# SNES_PicoCIC_v1_0.net
KiCad netlist of a schematic drawn in Altium Designer
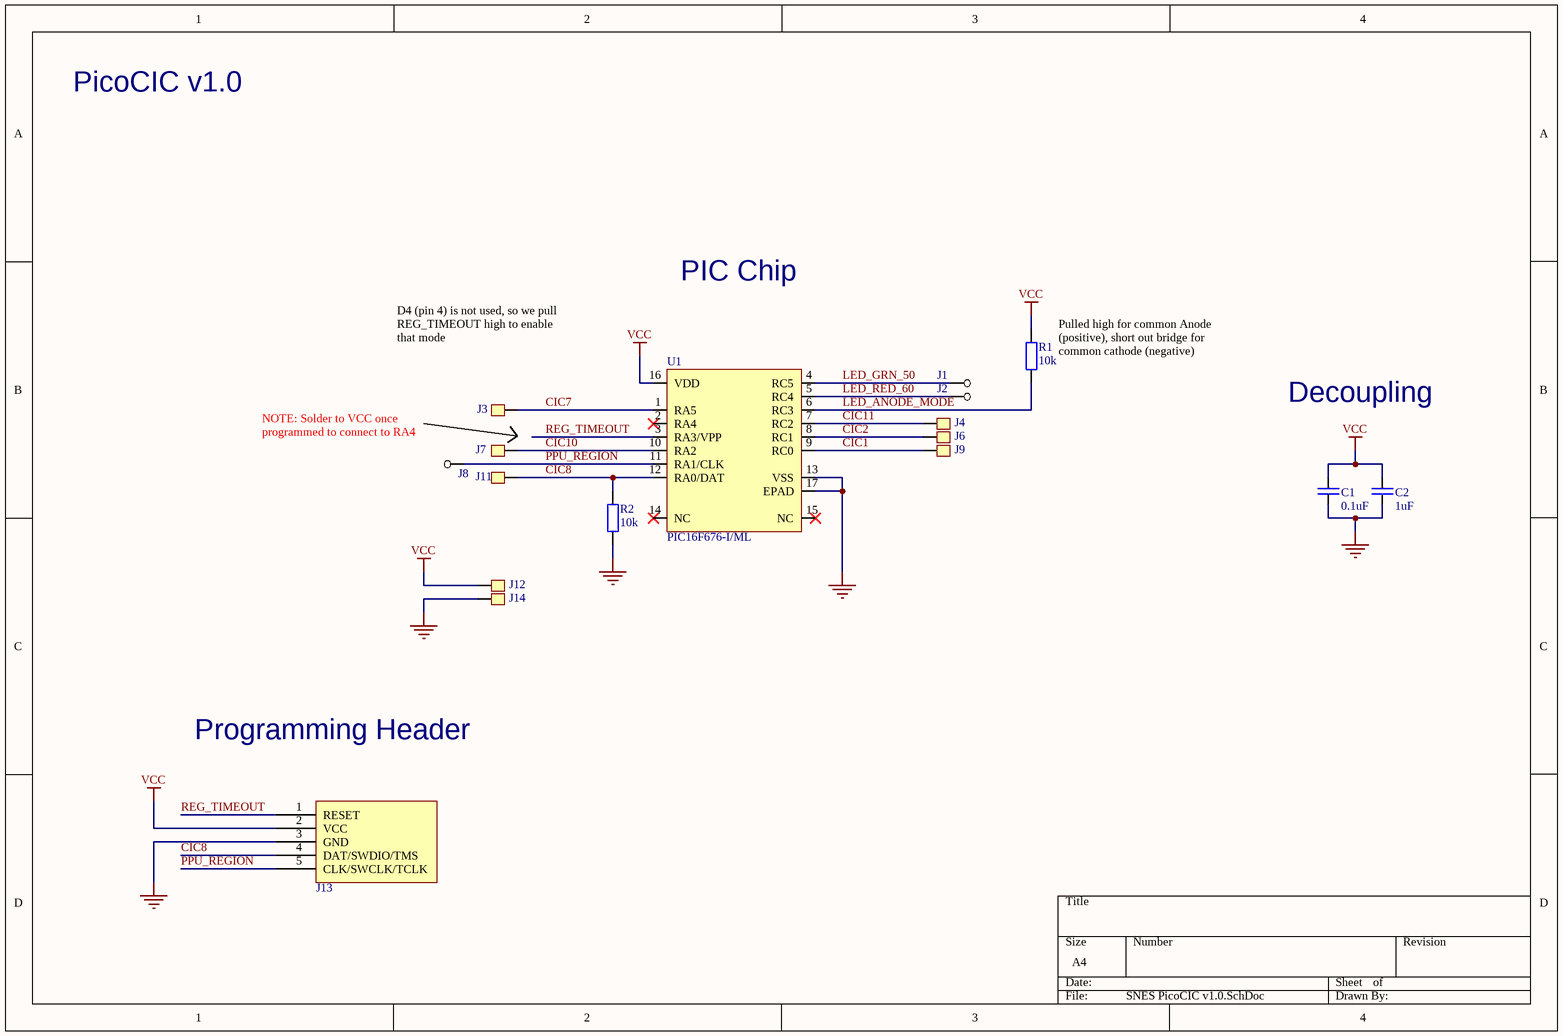
[diagram p0: SNES PicoCIC v1.0.SchDoc]

(export (version "E")
  (design (tool "Eeschema 10.0.6"))
  (components
    (comp (ref "C1")
      (value "0.1uF")
      (footprint "C0402")
      (description "Capacitor Ceramic 0.1uF 16V X5R 0402")
      (fields
        (field (name "MANUFACTURER") "Yageo")
        (field (name "MANUFACTURER PART NUMBER") "CC0402KRX7R7BB104")
      )
      (libsource (lib "Integrated_Library") (part "CAP_0UF1_0402"))
    )
    (comp (ref "C2")
      (value "1uF")
      (footprint "C0402")
      (description "Capacitor Ceramic 1uF 10V X5R 0402")
      (fields
        (field (name "MANUFACTURER") "Murata Electronics North America")
        (field (name "MANUFACTURER PART NUMBER") "GRM155R61A105KE15D")
      )
      (libsource (lib "Integrated_Library") (part "CAP_1UF_0402"))
    )
    (comp (ref "J1")
      (value "SP")
      (footprint "SP1.5")
      (description "Solder pad")
      (libsource (lib "Integrated_Library") (part "SP"))
    )
    (comp (ref "J2")
      (value "SP")
      (footprint "SP1.5")
      (description "Solder pad")
      (libsource (lib "Integrated_Library") (part "SP"))
    )
    (comp (ref "J3")
      (value "0.8MM Castellated Pad")
      (footprint "0.8MM CASTELLATED PAD")
      (description "Castellated pad for 0.8mm pitch")
      (libsource (lib "") (part "0.8MM Castellated Pad_1"))
    )
    (comp (ref "J4")
      (value "0.8MM Castellated Pad")
      (footprint "0.8MM CASTELLATED PAD")
      (description "Castellated pad for 0.8mm pitch")
      (libsource (lib "Integrated_Library") (part "0.8MM Castellated Pad"))
    )
    (comp (ref "J6")
      (value "0.8MM Castellated Pad")
      (footprint "0.8MM CASTELLATED PAD")
      (description "Castellated pad for 0.8mm pitch")
      (libsource (lib "Integrated_Library") (part "0.8MM Castellated Pad"))
    )
    (comp (ref "J7")
      (value "0.8MM Castellated Pad")
      (footprint "0.8MM CASTELLATED PAD")
      (description "Castellated pad for 0.8mm pitch")
      (libsource (lib "") (part "0.8MM Castellated Pad_1"))
    )
    (comp (ref "J8")
      (value "SP")
      (footprint "SP1.5")
      (description "Solder pad")
      (libsource (lib "Integrated_Library") (part "SP"))
    )
    (comp (ref "J9")
      (value "0.8MM Castellated Pad")
      (footprint "0.8MM CASTELLATED PAD")
      (description "Castellated pad for 0.8mm pitch")
      (libsource (lib "Integrated_Library") (part "0.8MM Castellated Pad"))
    )
    (comp (ref "J11")
      (value "0.8MM Castellated Pad")
      (footprint "0.8MM CASTELLATED PAD")
      (description "Castellated pad for 0.8mm pitch")
      (libsource (lib "") (part "0.8MM Castellated Pad_1"))
    )
    (comp (ref "J12")
      (value "0.8MM Castellated Pad")
      (footprint "0.8MM CASTELLATED PAD")
      (description "Castellated pad for 0.8mm pitch")
      (libsource (lib "Integrated_Library") (part "0.8MM Castellated Pad"))
    )
    (comp (ref "J13")
      (value "JTAG-SWD2")
      (footprint "JTAG-SWD 1.28mm")
      (description "JTAG-SWD Connector")
      (libsource (lib "Integrated_Library") (part "JTAG-SWD2"))
    )
    (comp (ref "J14")
      (value "0.8MM Castellated Pad")
      (footprint "0.8MM CASTELLATED PAD")
      (description "Castellated pad for 0.8mm pitch")
      (libsource (lib "Integrated_Library") (part "0.8MM Castellated Pad"))
    )
    (comp (ref "R1")
      (value "10k")
      (footprint "R0201")
      (description "Resistor 10k 0.05W 0201")
      (fields
        (field (name "MANUFACTURER") "Yageo")
        (field (name "MANUFACTURER PART NUMBER") "RC0201JR-0710KL")
      )
      (libsource (lib "Integrated_Library") (part "RES_10K_0201"))
    )
    (comp (ref "R2")
      (value "10k")
      (footprint "R0201")
      (description "Resistor 10k 0.05W 0201")
      (fields
        (field (name "MANUFACTURER") "Yageo")
        (field (name "MANUFACTURER PART NUMBER") "RC0201JR-0710KL")
      )
      (libsource (lib "Integrated_Library") (part "RES_10K_0201"))
    )
    (comp (ref "U1")
      (value "PIC16F676-I/ML")
      (footprint "QFN-16 4X4")
      (description "MCU 8-bit PIC RISC 1.75KB Flash 2.5V/3.3V/5V Automotive 16-Pin QFN EP Tube")
      (fields (field (name "MANUFACTURER") "Microchip"))
      (libsource (lib "Integrated_Library") (part "PIC16F676-I/ML"))
    )
  )
  (nets
    (net (code "1") (name "/CIC1") (class "Default")
      (node (ref "J9") (pin "1") (pinfunction "1_1") (pintype "passive"))
      (node (ref "U1") (pin "9") (pinfunction "RC0_9") (pintype "passive"))
    )
    (net (code "2") (name "/CIC2") (class "Default")
      (node (ref "J6") (pin "1") (pinfunction "1_1") (pintype "passive"))
      (node (ref "U1") (pin "8") (pinfunction "RC1_8") (pintype "passive"))
    )
    (net (code "3") (name "/CIC7") (class "Default")
      (node (ref "J3") (pin "1") (pinfunction "1_1") (pintype "passive"))
      (node (ref "U1") (pin "1") (pinfunction "RA5_1") (pintype "passive"))
    )
    (net (code "4") (name "/CIC8") (class "Default")
      (node (ref "J11") (pin "1") (pinfunction "1_1") (pintype "passive"))
      (node (ref "J13") (pin "4") (pinfunction "DAT/SWDIO/TMS_4") (pintype "passive"))
      (node (ref "R2") (pin "2") (pinfunction "2_2") (pintype "passive"))
      (node (ref "U1") (pin "12") (pinfunction "RA0/DAT_12") (pintype "passive"))
    )
    (net (code "5") (name "/CIC10") (class "Default")
      (node (ref "J7") (pin "1") (pinfunction "1_1") (pintype "passive"))
      (node (ref "U1") (pin "10") (pinfunction "RA2_10") (pintype "passive"))
    )
    (net (code "6") (name "/CIC11") (class "Default")
      (node (ref "J4") (pin "1") (pinfunction "1_1") (pintype "passive"))
      (node (ref "U1") (pin "7") (pinfunction "RC2_7") (pintype "passive"))
    )
    (net (code "7") (name "/LED_ANODE_MODE") (class "Default")
      (node (ref "R1") (pin "1") (pinfunction "1_1") (pintype "passive"))
      (node (ref "U1") (pin "6") (pinfunction "RC3_6") (pintype "passive"))
    )
    (net (code "8") (name "/LED_GRN_50") (class "Default")
      (node (ref "J1") (pin "1") (pinfunction "1_1") (pintype "passive"))
      (node (ref "U1") (pin "4") (pinfunction "RC5_4") (pintype "passive"))
    )
    (net (code "9") (name "/LED_RED_60") (class "Default")
      (node (ref "J2") (pin "1") (pinfunction "1_1") (pintype "passive"))
      (node (ref "U1") (pin "5") (pinfunction "RC4_5") (pintype "passive"))
    )
    (net (code "10") (name "/PPU_REGION") (class "Default")
      (node (ref "J13") (pin "5") (pinfunction "CLK/SWCLK/TCLK_5") (pintype "passive"))
      (node (ref "J8") (pin "1") (pinfunction "1_1") (pintype "passive"))
      (node (ref "U1") (pin "11") (pinfunction "RA1/CLK_11") (pintype "passive"))
    )
    (net (code "11") (name "/REG_TIMEOUT") (class "Default")
      (node (ref "J13") (pin "1") (pinfunction "RESET_1") (pintype "passive"))
      (node (ref "U1") (pin "3") (pinfunction "RA3/VPP_3") (pintype "passive"))
    )
    (net (code "12") (name "GND") (class "Default")
      (node (ref "C1") (pin "1") (pinfunction "1_1") (pintype "passive"))
      (node (ref "C2") (pin "1") (pinfunction "1_1") (pintype "passive"))
      (node (ref "J13") (pin "3") (pinfunction "GND_3") (pintype "passive"))
      (node (ref "J14") (pin "1") (pinfunction "1_1") (pintype "passive"))
      (node (ref "R2") (pin "1") (pinfunction "1_1") (pintype "passive"))
      (node (ref "U1") (pin "13") (pinfunction "VSS_13") (pintype "passive"))
      (node (ref "U1") (pin "17") (pinfunction "EPAD_17") (pintype "passive"))
    )
    (net (code "13") (name "VCC") (class "Default")
      (node (ref "C1") (pin "2") (pinfunction "2_2") (pintype "passive"))
      (node (ref "C2") (pin "2") (pinfunction "2_2") (pintype "passive"))
      (node (ref "J12") (pin "1") (pinfunction "1_1") (pintype "passive"))
      (node (ref "J13") (pin "2") (pinfunction "VCC_2") (pintype "passive"))
      (node (ref "R1") (pin "2") (pinfunction "2_2") (pintype "passive"))
      (node (ref "U1") (pin "16") (pinfunction "VDD_16") (pintype "passive"))
    )
    (net (code "14") (name "unconnected-(U1-NC-Pad14)") (class "Default")
      (node (ref "U1") (pin "14") (pinfunction "NC_14") (pintype "passive+no_connect"))
    )
    (net (code "15") (name "unconnected-(U1-NC-Pad15)") (class "Default")
      (node (ref "U1") (pin "15") (pinfunction "NC_15") (pintype "passive+no_connect"))
    )
    (net (code "16") (name "unconnected-(U1-RA4-Pad2)") (class "Default")
      (node (ref "U1") (pin "2") (pinfunction "RA4_2") (pintype "passive+no_connect"))
    )
  )
)
